# Sheet1.net
KiCad netlist of a schematic drawn in Altium Designer
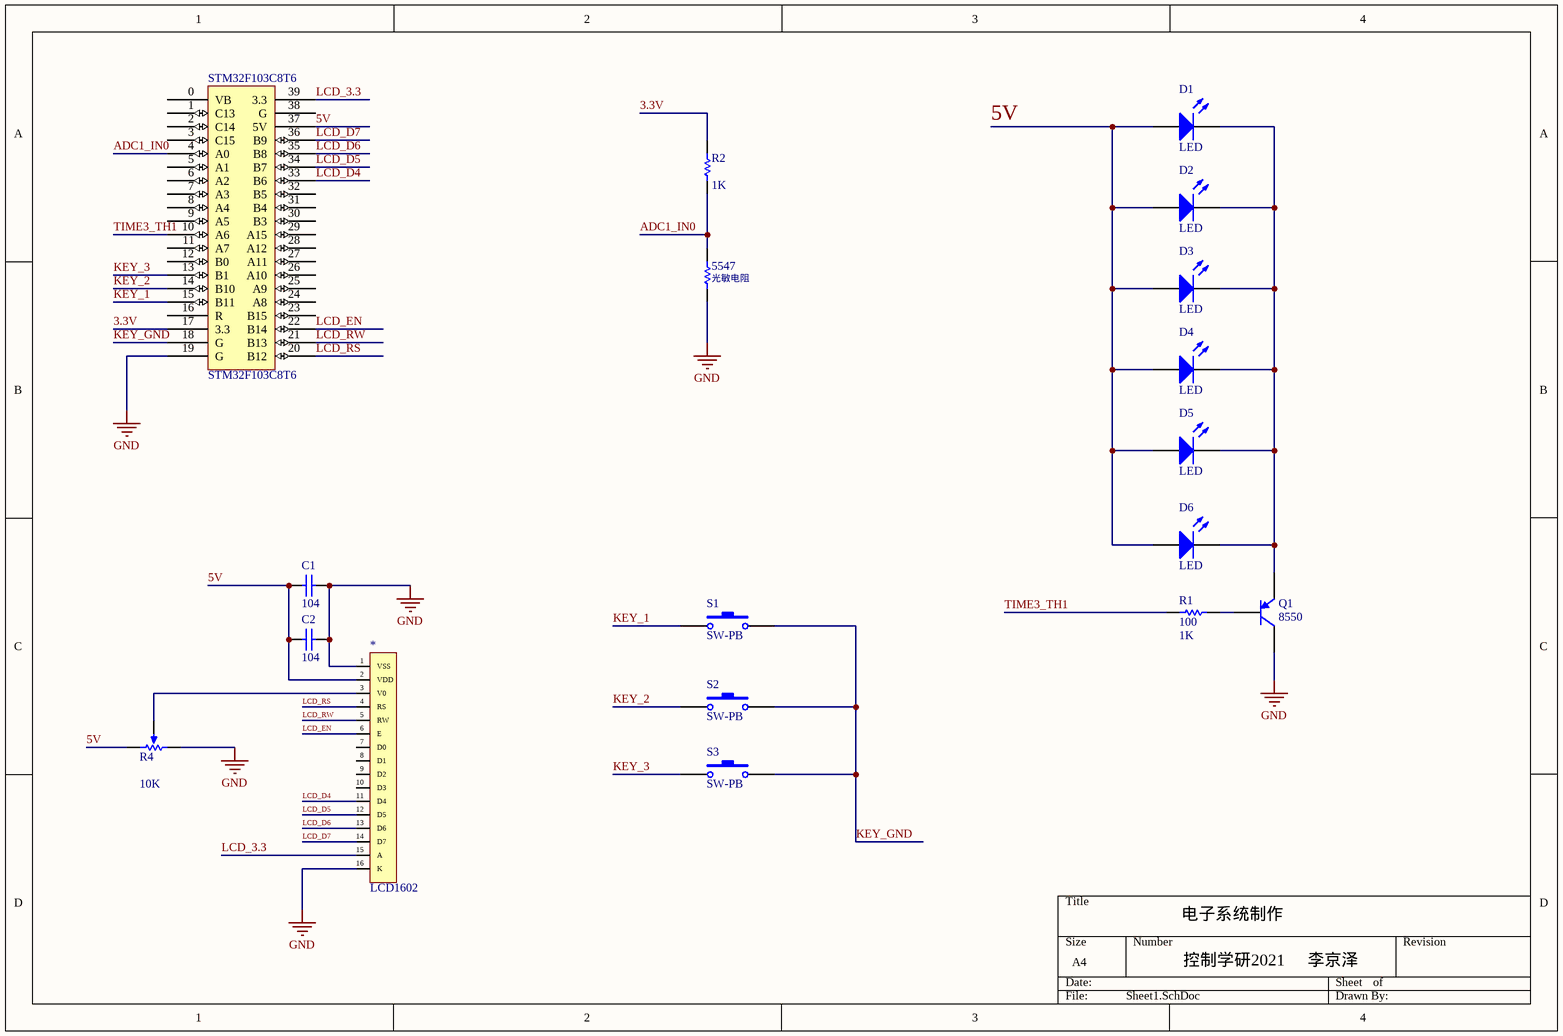
[diagram p0: Sheet1.SchDoc]

(export (version "E")
  (design (tool "Eeschema 10.0.6"))
  (components
    (comp (ref "*") (value "LCD1602") (footprint "HDR1X16") (libsource (lib "STM32F103") (part "LCD1602")))
    (comp (ref "5547")
      (value "光敏电阻")
      (footprint "R38")
      (description "Resistor")
      (fields (field (name "PUBLISHER") "Altium Limited"))
      (libsource (lib "Miscellaneous Devices") (part "Res1"))
    )
    (comp (ref "C1")
      (value "104")
      (footprint "RAD-0.3")
      (description "Capacitor")
      (fields (field (name "PUBLISHER") "Altium Limited"))
      (libsource (lib "Miscellaneous Devices") (part "Cap"))
    )
    (comp (ref "C2")
      (value "104")
      (footprint "RAD-0.3")
      (description "Capacitor")
      (fields (field (name "PUBLISHER") "Altium Limited"))
      (libsource (lib "Miscellaneous Devices") (part "Cap"))
    )
    (comp (ref "D1")
      (value "LED")
      (footprint "RB5-10.5")
      (description "Typical INFRARED GaAs LED")
      (fields (field (name "PUBLISHER") "Altium Limited"))
      (libsource (lib "Miscellaneous Devices") (part "LED0"))
    )
    (comp (ref "D2")
      (value "LED")
      (footprint "RB5-10.5")
      (description "Typical INFRARED GaAs LED")
      (fields (field (name "PUBLISHER") "Altium Limited"))
      (libsource (lib "Miscellaneous Devices") (part "LED0"))
    )
    (comp (ref "D3")
      (value "LED")
      (footprint "RB5-10.5")
      (description "Typical INFRARED GaAs LED")
      (fields (field (name "PUBLISHER") "Altium Limited"))
      (libsource (lib "Miscellaneous Devices") (part "LED0"))
    )
    (comp (ref "D4")
      (value "LED")
      (footprint "RB5-10.5")
      (description "Typical INFRARED GaAs LED")
      (fields (field (name "PUBLISHER") "Altium Limited"))
      (libsource (lib "Miscellaneous Devices") (part "LED0"))
    )
    (comp (ref "D5")
      (value "LED")
      (footprint "RB5-10.5")
      (description "Typical INFRARED GaAs LED")
      (fields (field (name "PUBLISHER") "Altium Limited"))
      (libsource (lib "Miscellaneous Devices") (part "LED0"))
    )
    (comp (ref "D6")
      (value "LED")
      (footprint "RB5-10.5")
      (description "Typical INFRARED GaAs LED")
      (fields (field (name "PUBLISHER") "Altium Limited"))
      (libsource (lib "Miscellaneous Devices") (part "LED0"))
    )
    (comp (ref "Q1")
      (value "8550")
      (footprint "TO-92A")
      (description "PNP Bipolar Transistor")
      (fields (field (name "PUBLISHER") "Altium Limited"))
      (libsource (lib "Miscellaneous Devices") (part "PNP"))
    )
    (comp (ref "R1")
      (value "100")
      (footprint "AXIAL-0.3")
      (description "Resistor")
      (fields (field (name "ALTIUM_VALUE") "1K") (field (name "PUBLISHER") "Altium Limited"))
      (libsource (lib "Miscellaneous Devices") (part "Res1"))
    )
    (comp (ref "R2")
      (value "1K")
      (footprint "AXIAL-0.3")
      (description "Resistor")
      (fields (field (name "Comment") "Res1") (field (name "PUBLISHER") "Altium Limited"))
      (libsource (lib "Miscellaneous Devices") (part "Res1"))
    )
    (comp (ref "R4")
      (value "10K")
      (footprint "TO-205AF")
      (description "Potentiometer")
      (fields (field (name "Comment") "RPot") (field (name "PUBLISHER") "Altium Limited"))
      (libsource (lib "Miscellaneous Devices") (part "RPot"))
    )
    (comp (ref "S1")
      (value "SW-PB")
      (footprint "DPST-4")
      (description "Switch")
      (fields (field (name "PUBLISHER") "Altium Limited"))
      (libsource (lib "Miscellaneous Devices") (part "SW-PB"))
    )
    (comp (ref "S2")
      (value "SW-PB")
      (footprint "DPST-4")
      (description "Switch")
      (fields (field (name "PUBLISHER") "Altium Limited"))
      (libsource (lib "Miscellaneous Devices") (part "SW-PB"))
    )
    (comp (ref "S3")
      (value "SW-PB")
      (footprint "DPST-4")
      (description "Switch")
      (fields (field (name "PUBLISHER") "Altium Limited"))
      (libsource (lib "Miscellaneous Devices") (part "SW-PB"))
    )
    (comp (ref "STM32F103C8T6")
      (value "STM32F103C8T6")
      (footprint "HDR1X20")
      (libsource (lib "STM32F103") (part "STM32F103C8T6"))
    )
  )
  (nets
    (net (code "1") (name "/3.3V") (class "Default")
      (node (ref "R2") (pin "2") (pinfunction "2_2") (pintype "passive"))
      (node (ref "STM32F103C8T6") (pin "17") (pinfunction "3.3_17") (pintype "power_in"))
    )
    (net (code "2") (name "/5V") (class "Default")
      (node (ref "*") (pin "2") (pinfunction "VDD_2") (pintype "passive"))
      (node (ref "C1") (pin "1") (pinfunction "1_1") (pintype "passive"))
      (node (ref "C2") (pin "2") (pinfunction "2_2") (pintype "passive"))
      (node (ref "D1") (pin "1") (pinfunction "A_1") (pintype "passive"))
      (node (ref "D2") (pin "1") (pinfunction "A_1") (pintype "passive"))
      (node (ref "D3") (pin "1") (pinfunction "A_1") (pintype "passive"))
      (node (ref "D4") (pin "1") (pinfunction "A_1") (pintype "passive"))
      (node (ref "D5") (pin "1") (pinfunction "A_1") (pintype "passive"))
      (node (ref "D6") (pin "1") (pinfunction "A_1") (pintype "passive"))
      (node (ref "R4") (pin "2") (pinfunction "BOT_2") (pintype "passive"))
      (node (ref "STM32F103C8T6") (pin "37") (pinfunction "5V_37") (pintype "power_in"))
    )
    (net (code "3") (name "/ADC1_IN0") (class "Default")
      (node (ref "5547") (pin "2") (pinfunction "2_2") (pintype "passive"))
      (node (ref "R2") (pin "1") (pinfunction "1_1") (pintype "passive"))
      (node (ref "STM32F103C8T6") (pin "4") (pinfunction "A0_4") (pintype "bidirectional"))
    )
    (net (code "4") (name "/KEY_1") (class "Default")
      (node (ref "S1") (pin "1") (pinfunction "1_1") (pintype "passive"))
      (node (ref "STM32F103C8T6") (pin "15") (pinfunction "B11_15") (pintype "bidirectional"))
    )
    (net (code "5") (name "/KEY_2") (class "Default")
      (node (ref "S2") (pin "1") (pinfunction "1_1") (pintype "passive"))
      (node (ref "STM32F103C8T6") (pin "14") (pinfunction "B10_14") (pintype "bidirectional"))
    )
    (net (code "6") (name "/KEY_3") (class "Default")
      (node (ref "S3") (pin "1") (pinfunction "1_1") (pintype "passive"))
      (node (ref "STM32F103C8T6") (pin "13") (pinfunction "B1_13") (pintype "bidirectional"))
    )
    (net (code "7") (name "/KEY_GND") (class "Default")
      (node (ref "S1") (pin "2") (pinfunction "2_2") (pintype "passive"))
      (node (ref "S2") (pin "2") (pinfunction "2_2") (pintype "passive"))
      (node (ref "S3") (pin "2") (pinfunction "2_2") (pintype "passive"))
      (node (ref "STM32F103C8T6") (pin "18") (pinfunction "G_18") (pintype "power_in"))
    )
    (net (code "8") (name "/LCD_3.3") (class "Default")
      (node (ref "*") (pin "15") (pinfunction "A_15") (pintype "passive"))
      (node (ref "STM32F103C8T6") (pin "39") (pinfunction "3.3_39") (pintype "power_in"))
    )
    (net (code "9") (name "/LCD_D4") (class "Default")
      (node (ref "*") (pin "11") (pinfunction "D4_11") (pintype "passive"))
      (node (ref "STM32F103C8T6") (pin "33") (pinfunction "B6_33") (pintype "bidirectional"))
    )
    (net (code "10") (name "/LCD_D5") (class "Default")
      (node (ref "*") (pin "12") (pinfunction "D5_12") (pintype "passive"))
      (node (ref "STM32F103C8T6") (pin "34") (pinfunction "B7_34") (pintype "bidirectional"))
    )
    (net (code "11") (name "/LCD_D6") (class "Default")
      (node (ref "*") (pin "13") (pinfunction "D6_13") (pintype "passive"))
      (node (ref "STM32F103C8T6") (pin "35") (pinfunction "B8_35") (pintype "bidirectional"))
    )
    (net (code "12") (name "/LCD_D7") (class "Default")
      (node (ref "*") (pin "14") (pinfunction "D7_14") (pintype "passive"))
      (node (ref "STM32F103C8T6") (pin "36") (pinfunction "B9_36") (pintype "bidirectional"))
    )
    (net (code "13") (name "/LCD_EN") (class "Default")
      (node (ref "*") (pin "6") (pinfunction "E_6") (pintype "passive"))
      (node (ref "STM32F103C8T6") (pin "22") (pinfunction "B14_22") (pintype "bidirectional"))
    )
    (net (code "14") (name "/LCD_RS") (class "Default")
      (node (ref "*") (pin "4") (pinfunction "RS_4") (pintype "passive"))
      (node (ref "STM32F103C8T6") (pin "20") (pinfunction "B12_20") (pintype "bidirectional"))
    )
    (net (code "15") (name "/LCD_RW") (class "Default")
      (node (ref "*") (pin "5") (pinfunction "RW_5") (pintype "passive"))
      (node (ref "STM32F103C8T6") (pin "21") (pinfunction "B13_21") (pintype "bidirectional"))
    )
    (net (code "16") (name "/TIME3_TH1") (class "Default")
      (node (ref "R1") (pin "1") (pinfunction "1_1") (pintype "passive"))
      (node (ref "STM32F103C8T6") (pin "10") (pinfunction "A6_10") (pintype "bidirectional"))
    )
    (net (code "17") (name "GND") (class "Default")
      (node (ref "*") (pin "1") (pinfunction "VSS_1") (pintype "passive"))
      (node (ref "*") (pin "16") (pinfunction "K_16") (pintype "passive"))
      (node (ref "5547") (pin "1") (pinfunction "1_1") (pintype "passive"))
      (node (ref "C1") (pin "2") (pinfunction "2_2") (pintype "passive"))
      (node (ref "C2") (pin "1") (pinfunction "1_1") (pintype "passive"))
      (node (ref "Q1") (pin "1") (pinfunction "C_1") (pintype "passive"))
      (node (ref "R4") (pin "1") (pinfunction "TOP_1") (pintype "passive"))
      (node (ref "STM32F103C8T6") (pin "19") (pinfunction "G_19") (pintype "power_in"))
    )
    (net (code "18") (name "Net-(*-V0)") (class "Default")
      (node (ref "*") (pin "3") (pinfunction "V0_3") (pintype "passive"))
      (node (ref "R4") (pin "3") (pinfunction "TAP_3") (pintype "passive"))
    )
    (net (code "19") (name "Net-(D1-K)") (class "Default")
      (node (ref "D1") (pin "2") (pinfunction "K_2") (pintype "passive"))
      (node (ref "D2") (pin "2") (pinfunction "K_2") (pintype "passive"))
      (node (ref "D3") (pin "2") (pinfunction "K_2") (pintype "passive"))
      (node (ref "D4") (pin "2") (pinfunction "K_2") (pintype "passive"))
      (node (ref "D5") (pin "2") (pinfunction "K_2") (pintype "passive"))
      (node (ref "D6") (pin "2") (pinfunction "K_2") (pintype "passive"))
      (node (ref "Q1") (pin "3") (pinfunction "E_3") (pintype "passive"))
    )
    (net (code "20") (name "Net-(Q1-B)") (class "Default")
      (node (ref "Q1") (pin "2") (pinfunction "B_2") (pintype "passive"))
      (node (ref "R1") (pin "2") (pinfunction "2_2") (pintype "passive"))
    )
    (net (code "21") (name "unconnected-(*-D0-Pad7)") (class "Default")
      (node (ref "*") (pin "7") (pinfunction "D0_7") (pintype "passive"))
    )
    (net (code "22") (name "unconnected-(*-D1-Pad8)") (class "Default")
      (node (ref "*") (pin "8") (pinfunction "D1_8") (pintype "passive"))
    )
    (net (code "23") (name "unconnected-(*-D2-Pad9)") (class "Default")
      (node (ref "*") (pin "9") (pinfunction "D2_9") (pintype "passive"))
    )
    (net (code "24") (name "unconnected-(*-D3-Pad10)") (class "Default")
      (node (ref "*") (pin "10") (pinfunction "D3_10") (pintype "passive"))
    )
    (net (code "25") (name "unconnected-(STM32F103C8T6-A1-Pad5)") (class "Default")
      (node (ref "STM32F103C8T6") (pin "5") (pinfunction "A1_5") (pintype "bidirectional"))
    )
    (net (code "26") (name "unconnected-(STM32F103C8T6-A2-Pad6)") (class "Default")
      (node (ref "STM32F103C8T6") (pin "6") (pinfunction "A2_6") (pintype "bidirectional"))
    )
    (net (code "27") (name "unconnected-(STM32F103C8T6-A3-Pad7)") (class "Default")
      (node (ref "STM32F103C8T6") (pin "7") (pinfunction "A3_7") (pintype "bidirectional"))
    )
    (net (code "28") (name "unconnected-(STM32F103C8T6-A4-Pad8)") (class "Default")
      (node (ref "STM32F103C8T6") (pin "8") (pinfunction "A4_8") (pintype "bidirectional"))
    )
    (net (code "29") (name "unconnected-(STM32F103C8T6-A5-Pad9)") (class "Default")
      (node (ref "STM32F103C8T6") (pin "9") (pinfunction "A5_9") (pintype "bidirectional"))
    )
    (net (code "30") (name "unconnected-(STM32F103C8T6-A7-Pad11)") (class "Default")
      (node (ref "STM32F103C8T6") (pin "11") (pinfunction "A7_11") (pintype "bidirectional"))
    )
    (net (code "31") (name "unconnected-(STM32F103C8T6-A8-Pad24)") (class "Default")
      (node (ref "STM32F103C8T6") (pin "24") (pinfunction "A8_24") (pintype "bidirectional"))
    )
    (net (code "32") (name "unconnected-(STM32F103C8T6-A9-Pad25)") (class "Default")
      (node (ref "STM32F103C8T6") (pin "25") (pinfunction "A9_25") (pintype "bidirectional"))
    )
    (net (code "33") (name "unconnected-(STM32F103C8T6-A10-Pad26)") (class "Default")
      (node (ref "STM32F103C8T6") (pin "26") (pinfunction "A10_26") (pintype "bidirectional"))
    )
    (net (code "34") (name "unconnected-(STM32F103C8T6-A11-Pad27)") (class "Default")
      (node (ref "STM32F103C8T6") (pin "27") (pinfunction "A11_27") (pintype "bidirectional"))
    )
    (net (code "35") (name "unconnected-(STM32F103C8T6-A12-Pad28)") (class "Default")
      (node (ref "STM32F103C8T6") (pin "28") (pinfunction "A12_28") (pintype "bidirectional"))
    )
    (net (code "36") (name "unconnected-(STM32F103C8T6-A15-Pad29)") (class "Default")
      (node (ref "STM32F103C8T6") (pin "29") (pinfunction "A15_29") (pintype "bidirectional"))
    )
    (net (code "37") (name "unconnected-(STM32F103C8T6-B0-Pad12)") (class "Default")
      (node (ref "STM32F103C8T6") (pin "12") (pinfunction "B0_12") (pintype "bidirectional"))
    )
    (net (code "38") (name "unconnected-(STM32F103C8T6-B3-Pad30)") (class "Default")
      (node (ref "STM32F103C8T6") (pin "30") (pinfunction "B3_30") (pintype "bidirectional"))
    )
    (net (code "39") (name "unconnected-(STM32F103C8T6-B4-Pad31)") (class "Default")
      (node (ref "STM32F103C8T6") (pin "31") (pinfunction "B4_31") (pintype "bidirectional"))
    )
    (net (code "40") (name "unconnected-(STM32F103C8T6-B5-Pad32)") (class "Default")
      (node (ref "STM32F103C8T6") (pin "32") (pinfunction "B5_32") (pintype "bidirectional"))
    )
    (net (code "41") (name "unconnected-(STM32F103C8T6-B15-Pad23)") (class "Default")
      (node (ref "STM32F103C8T6") (pin "23") (pinfunction "B15_23") (pintype "bidirectional"))
    )
    (net (code "42") (name "unconnected-(STM32F103C8T6-C13-Pad1)") (class "Default")
      (node (ref "STM32F103C8T6") (pin "1") (pinfunction "C13_1") (pintype "bidirectional"))
    )
    (net (code "43") (name "unconnected-(STM32F103C8T6-C14-Pad2)") (class "Default")
      (node (ref "STM32F103C8T6") (pin "2") (pinfunction "C14_2") (pintype "bidirectional"))
    )
    (net (code "44") (name "unconnected-(STM32F103C8T6-C15-Pad3)") (class "Default")
      (node (ref "STM32F103C8T6") (pin "3") (pinfunction "C15_3") (pintype "bidirectional"))
    )
    (net (code "45") (name "unconnected-(STM32F103C8T6-G-Pad38)") (class "Default")
      (node (ref "STM32F103C8T6") (pin "38") (pinfunction "G_38") (pintype "power_in"))
    )
    (net (code "46") (name "unconnected-(STM32F103C8T6-R-Pad16)") (class "Default")
      (node (ref "STM32F103C8T6") (pin "16") (pinfunction "R_16") (pintype "passive"))
    )
    (net (code "47") (name "unconnected-(STM32F103C8T6-VB-Pad0)") (class "Default")
      (node (ref "STM32F103C8T6") (pin "0") (pinfunction "VB_0") (pintype "passive"))
    )
  )
)
